# MemoriaCalibrado.net
KiCad netlist of a schematic drawn in EAGLE
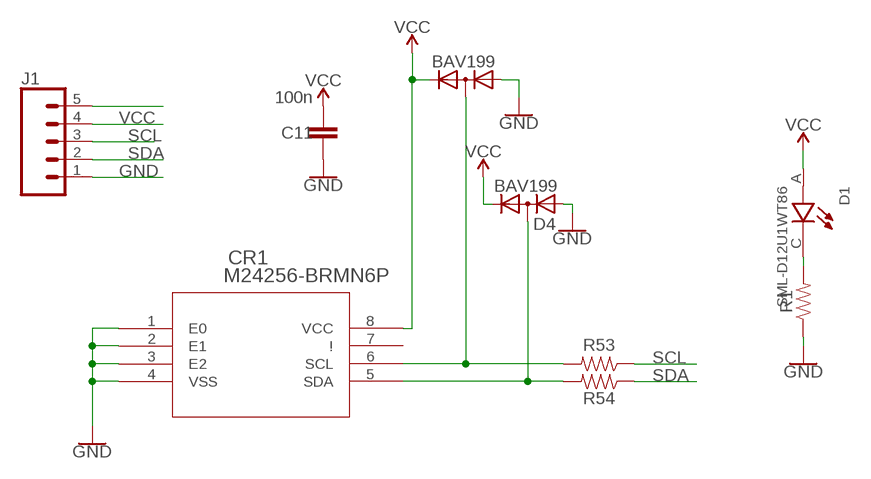
[diagram p0: schematic, sheet 1]

(export (version "E")
  (design (tool "Eeschema 10.0.6"))
  (components
    (comp (ref "C11")
      (value "100n")
      (footprint "eagle-import:0805")
      (libsource (lib "eagle-import") (part "1.0UF-0805-25V-(+80/-20%)"))
    )
    (comp (ref "CR1")
      (value "M24256-BRMN6P")
      (footprint "eagle-import:SO-8_STM")
      (fields (field (name "COPYRIGHT") "Copyright (C) 2024 Ultra Librarian. All rights reserved."))
      (libsource (lib "eagle-import") (part "M24256-BRMN6P"))
    )
    (comp (ref "D1")
      (value "SML-D12U1WT86")
      (footprint "eagle-import:LED_SML-D12U1WT86")
      (fields (field (name "DIGIKEY_PART_NUMBER") "SML-D12U1WT86TR-ND") (field (name "MF") "Rohm"))
      (libsource (lib "eagle-import") (part "SML-D12U1WT86"))
    )
    (comp (ref "D4")
      (value "BAV199")
      (footprint "eagle-import:SOT23")
      (libsource (lib "eagle-import") (part "BAV199"))
    )
    (comp (ref "D5")
      (value "BAV199")
      (footprint "eagle-import:SOT23")
      (libsource (lib "eagle-import") (part "BAV199"))
    )
    (comp (ref "J1")
      (value "CONN_05")
      (footprint "eagle-import:1X05")
      (libsource (lib "eagle-import") (part "CONN_05"))
    )
    (comp (ref "R1")
      (value "RESISTOR0805")
      (footprint "eagle-import:0805")
      (libsource (lib "eagle-import") (part "RESISTOR0805"))
    )
    (comp (ref "R53")
      (value "RESISTOR0805")
      (footprint "eagle-import:0805")
      (libsource (lib "eagle-import") (part "RESISTOR0805"))
    )
    (comp (ref "R54")
      (value "RESISTOR0805")
      (footprint "eagle-import:0805")
      (libsource (lib "eagle-import") (part "RESISTOR0805"))
    )
  )
  (nets
    (net (code "1") (name "/SCL") (class "Default")
      (node (ref "J1") (pin "3") (pinfunction "3_3") (pintype "passive"))
      (node (ref "R53") (pin "1") (pinfunction "1_1") (pintype "passive"))
    )
    (net (code "2") (name "/SDA") (class "Default")
      (node (ref "J1") (pin "2") (pinfunction "2_2") (pintype "passive"))
      (node (ref "R54") (pin "1") (pinfunction "1_1") (pintype "passive"))
    )
    (net (code "3") (name "GND") (class "Default")
      (node (ref "C11") (pin "1") (pinfunction "1_1") (pintype "passive"))
      (node (ref "CR1") (pin "1") (pinfunction "E0_1") (pintype "input"))
      (node (ref "CR1") (pin "2") (pinfunction "E1_2") (pintype "input"))
      (node (ref "CR1") (pin "3") (pinfunction "E2_3") (pintype "input"))
      (node (ref "CR1") (pin "4") (pinfunction "VSS_4") (pintype "power_in"))
      (node (ref "D4") (pin "1") (pinfunction "A_1") (pintype "passive"))
      (node (ref "D5") (pin "1") (pinfunction "A_1") (pintype "passive"))
      (node (ref "J1") (pin "1") (pinfunction "1_1") (pintype "passive"))
      (node (ref "R1") (pin "1") (pinfunction "1_1") (pintype "passive"))
    )
    (net (code "4") (name "Net-(CR1-SCL)") (class "Default")
      (node (ref "CR1") (pin "6") (pinfunction "SCL_6") (pintype "input"))
      (node (ref "D5") (pin "3") (pinfunction "AC_3") (pintype "passive"))
      (node (ref "R53") (pin "2") (pinfunction "2_2") (pintype "passive"))
    )
    (net (code "5") (name "Net-(CR1-SDA)") (class "Default")
      (node (ref "CR1") (pin "5") (pinfunction "SDA_5") (pintype "bidirectional"))
      (node (ref "D4") (pin "3") (pinfunction "AC_3") (pintype "passive"))
      (node (ref "R54") (pin "2") (pinfunction "2_2") (pintype "passive"))
    )
    (net (code "6") (name "Net-(D1-PadC)") (class "Default")
      (node (ref "D1") (pin "C") (pinfunction "C_C") (pintype "passive"))
      (node (ref "R1") (pin "2") (pinfunction "2_2") (pintype "passive"))
    )
    (net (code "7") (name "VCC") (class "Default")
      (node (ref "C11") (pin "2") (pinfunction "2_2") (pintype "passive"))
      (node (ref "CR1") (pin "8") (pinfunction "VCC_8") (pintype "power_in"))
      (node (ref "D1") (pin "A") (pinfunction "A_A") (pintype "passive"))
      (node (ref "D4") (pin "2") (pinfunction "C_2") (pintype "passive"))
      (node (ref "D5") (pin "2") (pinfunction "C_2") (pintype "passive"))
      (node (ref "J1") (pin "4") (pinfunction "4_4") (pintype "passive"))
    )
    (net (code "8") (name "unconnected-(CR1-~-Pad7)") (class "Default")
      (node (ref "CR1") (pin "7") (pinfunction "~_7") (pintype "input"))
    )
    (net (code "9") (name "unconnected-(J1-Pad5)") (class "Default")
      (node (ref "J1") (pin "5") (pinfunction "5_5") (pintype "passive"))
    )
  )
)
